# Root.net
KiCad netlist of a schematic drawn in Altium Designer
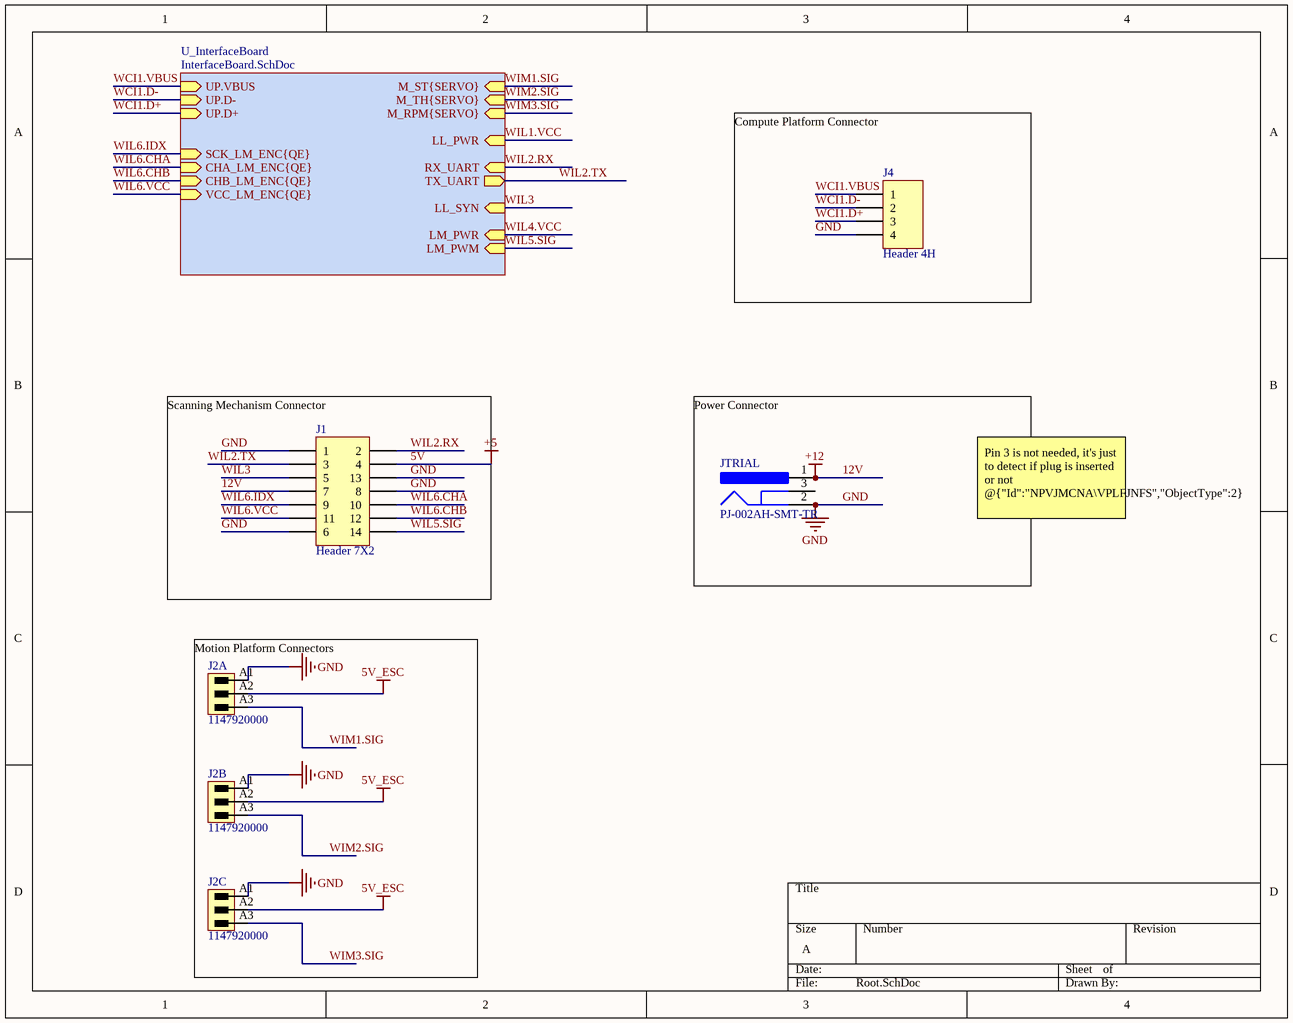
[diagram p0: Root.SchDoc]

(export (version "E")
  (design (tool "Eeschema 10.0.6"))
  (components
    (comp (ref "J1")
      (value "Header 7X2")
      (footprint "HDR2X7")
      (description "Header, 7-Pin, Dual row")
      (fields (field (name "PUBLISHER") "Altium Limited"))
      (libsource (lib "Isaac Lee Altium Cloud") (part "Copy of Header 7X2H"))
    )
    (comp (ref "J2A")
      (value "1147920000")
      (footprint "SL_5_08HC_180LF_03")
      (description "OMNIMATE Signal - series BL/SL 5.08")
      (fields (field (name "MANUFACTURER") "Weidmueller"))
      (libsource (lib "Altium Content Vault") (part "Header_Male_03_1x03"))
    )
    (comp (ref "J2B")
      (value "1147920000")
      (footprint "SL_5_08HC_180LF_03")
      (description "OMNIMATE Signal - series BL/SL 5.08")
      (fields (field (name "MANUFACTURER") "Weidmueller"))
      (libsource (lib "Altium Content Vault") (part "Header_Male_03_1x03"))
    )
    (comp (ref "J2C")
      (value "1147920000")
      (footprint "SL_5_08HC_180LF_03")
      (description "OMNIMATE Signal - series BL/SL 5.08")
      (fields (field (name "MANUFACTURER") "Weidmueller"))
      (libsource (lib "Altium Content Vault") (part "Header_Male_03_1x03"))
    )
    (comp (ref "J4")
      (value "Header 4H")
      (footprint "HDR1X4H")
      (description "Header, 4-Pin, Right Angle")
      (fields (field (name "PUBLISHER") "Altium Limited"))
      (libsource (lib "AutoLidar_VIP_Spring25") (part "Header 4H"))
    )
    (comp (ref "JTRIAL")
      (value "PJ-002AH-SMT-TR")
      (footprint "CUI-PJ-002AH-4_V")
      (description "DC Power Jack, Right Angle, -25 to 85 degC, 4-Pin 14.8 x 9 x 11 mm SMD, RoHS, Tape and Reel")
      (fields (field (name "MANUFACTURER") "CUIInc.") (field (name "PARTNUMBER") "PJ-002AH"))
      (libsource (lib "Altium Content Vault") (part "JACK-2CD3-RN_B"))
    )
  )
  (nets
    (net (code "1") (name "+5") (class "Default")
      (node (ref "J1") (pin "4") (pinfunction "4_4") (pintype "passive"))
    )
    (net (code "2") (name "+12") (class "Default")
      (node (ref "J1") (pin "7") (pinfunction "7_7") (pintype "passive"))
      (node (ref "JTRIAL") (pin "1") (pinfunction "1_1") (pintype "passive"))
    )
    (net (code "3") (name "/WCI1.D+") (class "Default")
      (node (ref "J4") (pin "3") (pinfunction "3_3") (pintype "passive"))
    )
    (net (code "4") (name "/WCI1.D-") (class "Default")
      (node (ref "J4") (pin "2") (pinfunction "2_2") (pintype "passive"))
    )
    (net (code "5") (name "/WCI1.VBUS") (class "Default")
      (node (ref "J4") (pin "1") (pinfunction "1_1") (pintype "passive"))
    )
    (net (code "7") (name "/WIL2.RX") (class "Default")
      (node (ref "J1") (pin "2") (pinfunction "2_2") (pintype "passive"))
    )
    (net (code "8") (name "/WIL2.TX") (class "Default")
      (node (ref "J1") (pin "3") (pinfunction "3_3") (pintype "passive"))
    )
    (net (code "9") (name "/WIL3") (class "Default")
      (node (ref "J1") (pin "5") (pinfunction "5_5") (pintype "passive"))
    )
    (net (code "11") (name "/WIL5.SIG") (class "Default")
      (node (ref "J1") (pin "14") (pinfunction "14_14") (pintype "passive"))
    )
    (net (code "12") (name "/WIL6.CHA") (class "Default")
      (node (ref "J1") (pin "10") (pinfunction "10_10") (pintype "passive"))
    )
    (net (code "13") (name "/WIL6.CHB") (class "Default")
      (node (ref "J1") (pin "12") (pinfunction "12_12") (pintype "passive"))
    )
    (net (code "14") (name "/WIL6.IDX") (class "Default")
      (node (ref "J1") (pin "9") (pinfunction "9_9") (pintype "passive"))
    )
    (net (code "15") (name "/WIL6.VCC") (class "Default")
      (node (ref "J1") (pin "11") (pinfunction "11_11") (pintype "passive"))
    )
    (net (code "16") (name "/WIM1.SIG") (class "Default")
      (node (ref "J2A") (pin "A3") (pinfunction "A3_A3") (pintype "passive"))
    )
    (net (code "17") (name "/WIM2.SIG") (class "Default")
      (node (ref "J2B") (pin "A3") (pinfunction "A3_A3") (pintype "passive"))
    )
    (net (code "18") (name "/WIM3.SIG") (class "Default")
      (node (ref "J2C") (pin "A3") (pinfunction "A3_A3") (pintype "passive"))
    )
    (net (code "19") (name "5V_ESC") (class "Default")
      (node (ref "J2A") (pin "A2") (pinfunction "A2_A2") (pintype "passive"))
      (node (ref "J2B") (pin "A2") (pinfunction "A2_A2") (pintype "passive"))
      (node (ref "J2C") (pin "A2") (pinfunction "A2_A2") (pintype "passive"))
    )
    (net (code "20") (name "GND") (class "Default")
      (node (ref "J1") (pin "1") (pinfunction "1_1") (pintype "passive"))
      (node (ref "J1") (pin "13") (pinfunction "13_13") (pintype "passive"))
      (node (ref "J1") (pin "6") (pinfunction "6_6") (pintype "passive"))
      (node (ref "J1") (pin "8") (pinfunction "8_8") (pintype "passive"))
      (node (ref "J2A") (pin "A1") (pinfunction "A1_A1") (pintype "passive"))
      (node (ref "J2B") (pin "A1") (pinfunction "A1_A1") (pintype "passive"))
      (node (ref "J2C") (pin "A1") (pinfunction "A1_A1") (pintype "passive"))
      (node (ref "J4") (pin "4") (pinfunction "4_4") (pintype "passive"))
      (node (ref "JTRIAL") (pin "2") (pinfunction "2_2") (pintype "passive"))
    )
    (net (code "21") (name "unconnected-(JTRIAL-Pad3)") (class "Default")
      (node (ref "JTRIAL") (pin "3") (pinfunction "3_3") (pintype "passive"))
    )
  )
)
